# rtc.net
KiCad netlist of a schematic drawn in Altium Designer
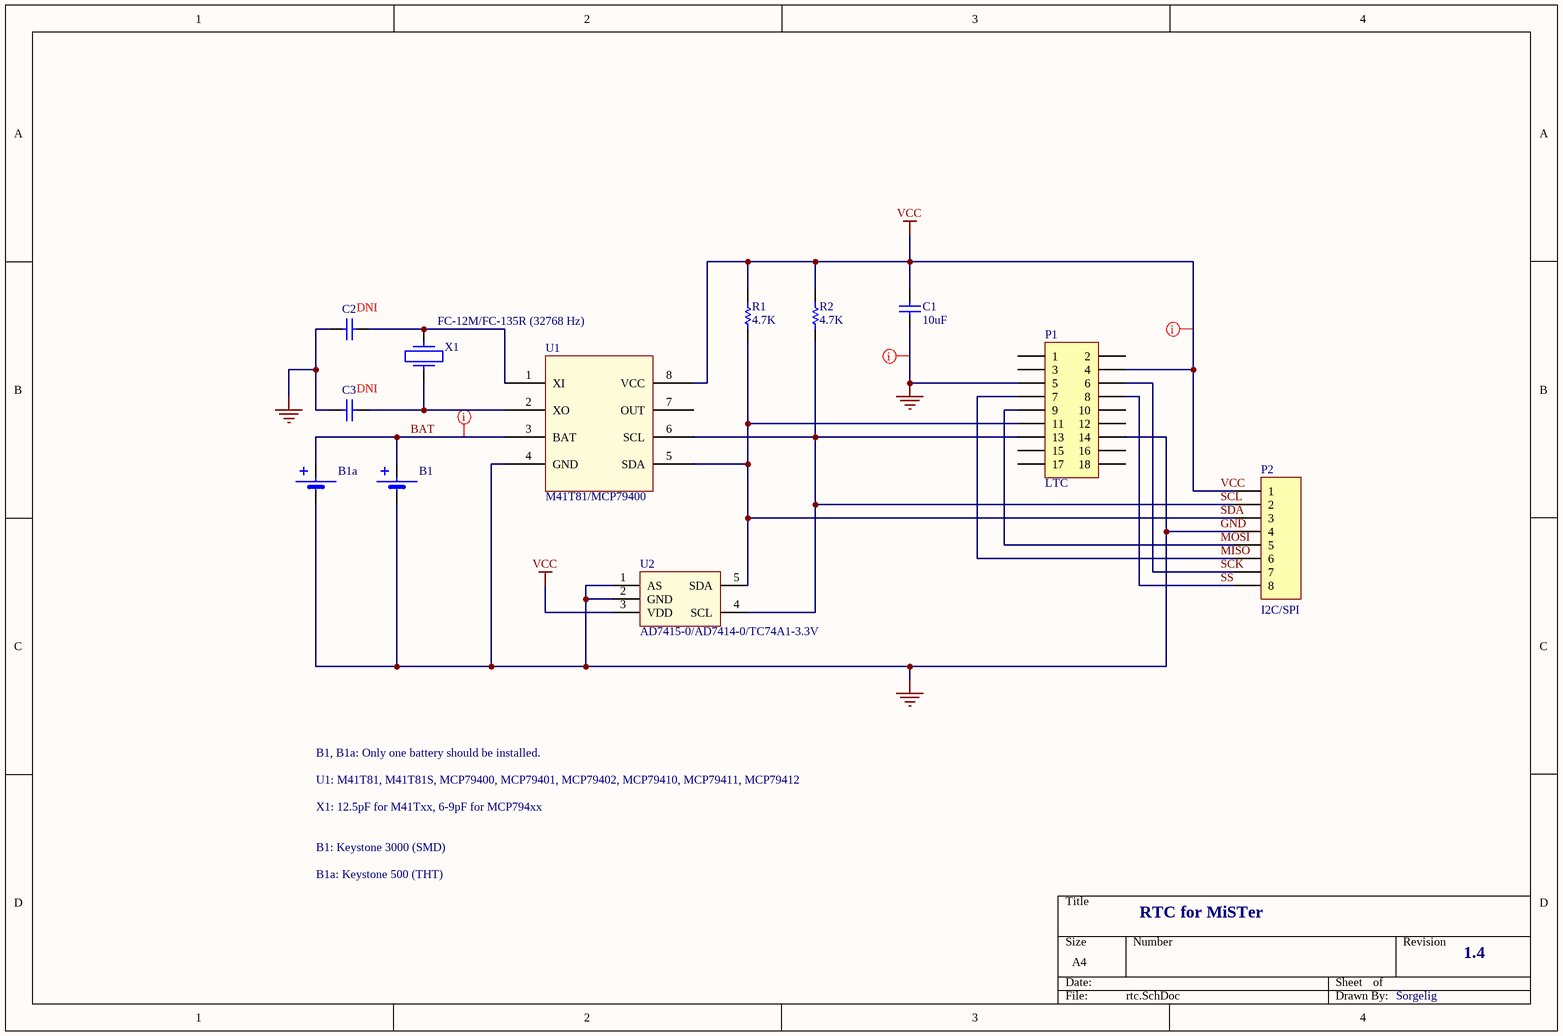
[diagram p0: rtc.SchDoc]

(export (version "E")
  (design (tool "Eeschema 10.0.6"))
  (components
    (comp (ref "B1") (value "*") (footprint "KS3000") (libsource (lib "lib") (part "BAT_KS3000")))
    (comp (ref "B1a") (value "BAT") (footprint "BAT") (libsource (lib "lib") (part "BAT")))
    (comp (ref "C1")
      (value "10uF")
      (footprint "C0805")
      (description "Ceramic Chip Capacitor - Standard")
      (fields (field (name "Comment") "C0805") (field (name "PUBLISHER") "Altium Limited"))
      (libsource (lib "KEMET Chip Capacitor") (part "C0805"))
    )
    (comp (ref "C2")
      (value "C0805")
      (footprint "0805")
      (description "Ceramic Chip Capacitor - Standard")
      (fields (field (name "PUBLISHER") "Altium Limited"))
      (libsource (lib "KEMET Chip Capacitor") (part "C0805"))
    )
    (comp (ref "C3")
      (value "C0805")
      (footprint "0805")
      (description "Ceramic Chip Capacitor - Standard")
      (fields (field (name "PUBLISHER") "Altium Limited"))
      (libsource (lib "KEMET Chip Capacitor") (part "C0805"))
    )
    (comp (ref "P1") (value "LTC") (footprint "hdr9x2") (libsource (lib "lib") (part "HDR9x2")))
    (comp (ref "P2")
      (value "I2C/SPI")
      (footprint "HDR1X8")
      (description "Header, 8-Pin")
      (fields (field (name "PUBLISHER") "Altium Limited"))
      (libsource (lib "Miscellaneous Connectors") (part "Header 8"))
    )
    (comp (ref "R1")
      (value "4.7K")
      (footprint "R0805")
      (fields (field (name "PUBLISHER") "Altium Limited"))
      (libsource (lib "lib") (part "ERJ6RS"))
    )
    (comp (ref "R2")
      (value "4.7K")
      (footprint "R0805")
      (fields (field (name "PUBLISHER") "Altium Limited"))
      (libsource (lib "lib") (part "ERJ6RS"))
    )
    (comp (ref "U1") (value "M41T81/MCP79400") (footprint "SOIC8P") (libsource (lib "lib") (part "M41T")))
    (comp (ref "U2")
      (value "AD7415-0/AD7414-0/TC74A1-3.3V")
      (footprint "SOT23-5")
      (libsource (lib "lib") (part "AD7415"))
    )
    (comp (ref "X1")
      (value "FC-12M/FC-135R (32768 Hz)")
      (footprint "OSC")
      (libsource (lib "lib") (part "OSC"))
    )
  )
  (nets
    (net (code "1") (name "/BAT") (class "Default")
      (node (ref "B1") (pin "2") (pinfunction "2_2") (pintype "passive"))
      (node (ref "B1a") (pin "2") (pinfunction "2_2") (pintype "passive"))
      (node (ref "U1") (pin "3") (pinfunction "BAT_3") (pintype "passive"))
    )
    (net (code "2") (name "/MISO") (class "Default")
      (node (ref "P1") (pin "7") (pinfunction "7_7") (pintype "passive"))
      (node (ref "P2") (pin "6") (pinfunction "6_6") (pintype "passive"))
    )
    (net (code "3") (name "/MOSI") (class "Default")
      (node (ref "P1") (pin "9") (pinfunction "9_9") (pintype "passive"))
      (node (ref "P2") (pin "5") (pinfunction "5_5") (pintype "passive"))
    )
    (net (code "4") (name "/SCK") (class "Default")
      (node (ref "P1") (pin "6") (pinfunction "6_6") (pintype "passive"))
      (node (ref "P2") (pin "7") (pinfunction "7_7") (pintype "passive"))
    )
    (net (code "5") (name "/SCL") (class "Default")
      (node (ref "P1") (pin "13") (pinfunction "13_13") (pintype "passive"))
      (node (ref "P2") (pin "2") (pinfunction "2_2") (pintype "passive"))
      (node (ref "R2") (pin "1") (pinfunction "1_1") (pintype "passive"))
      (node (ref "U1") (pin "6") (pinfunction "SCL_6") (pintype "passive"))
      (node (ref "U2") (pin "4") (pinfunction "SCL_4") (pintype "passive"))
    )
    (net (code "6") (name "/SDA") (class "Default")
      (node (ref "P1") (pin "11") (pinfunction "11_11") (pintype "passive"))
      (node (ref "P2") (pin "3") (pinfunction "3_3") (pintype "passive"))
      (node (ref "R1") (pin "1") (pinfunction "1_1") (pintype "passive"))
      (node (ref "U1") (pin "5") (pinfunction "SDA_5") (pintype "passive"))
      (node (ref "U2") (pin "5") (pinfunction "SDA_5") (pintype "passive"))
    )
    (net (code "7") (name "/SS") (class "Default")
      (node (ref "P1") (pin "8") (pinfunction "8_8") (pintype "passive"))
      (node (ref "P2") (pin "8") (pinfunction "8_8") (pintype "passive"))
    )
    (net (code "8") (name "GND") (class "Default")
      (node (ref "B1") (pin "1") (pinfunction "1_1") (pintype "passive"))
      (node (ref "B1a") (pin "1") (pinfunction "1_1") (pintype "passive"))
      (node (ref "C1") (pin "1") (pinfunction "1_1") (pintype "passive"))
      (node (ref "C2") (pin "1") (pinfunction "1_1") (pintype "passive"))
      (node (ref "C3") (pin "1") (pinfunction "1_1") (pintype "passive"))
      (node (ref "P1") (pin "14") (pinfunction "14_14") (pintype "passive"))
      (node (ref "P1") (pin "5") (pinfunction "5_5") (pintype "passive"))
      (node (ref "P2") (pin "4") (pinfunction "4_4") (pintype "passive"))
      (node (ref "U1") (pin "4") (pinfunction "GND_4") (pintype "passive"))
      (node (ref "U2") (pin "1") (pinfunction "AS_1") (pintype "passive"))
      (node (ref "U2") (pin "2") (pinfunction "GND_2") (pintype "passive"))
    )
    (net (code "9") (name "Net-(U1-XI)") (class "Default")
      (node (ref "C2") (pin "2") (pinfunction "2_2") (pintype "passive"))
      (node (ref "U1") (pin "1") (pinfunction "XI_1") (pintype "passive"))
      (node (ref "X1") (pin "1") (pinfunction "1_1") (pintype "passive"))
    )
    (net (code "10") (name "Net-(U1-XO)") (class "Default")
      (node (ref "C3") (pin "2") (pinfunction "2_2") (pintype "passive"))
      (node (ref "U1") (pin "2") (pinfunction "XO_2") (pintype "passive"))
      (node (ref "X1") (pin "2") (pinfunction "2_2") (pintype "passive"))
    )
    (net (code "11") (name "VCC") (class "Default")
      (node (ref "C1") (pin "2") (pinfunction "2_2") (pintype "passive"))
      (node (ref "P1") (pin "4") (pinfunction "4_4") (pintype "passive"))
      (node (ref "P2") (pin "1") (pinfunction "1_1") (pintype "passive"))
      (node (ref "R1") (pin "2") (pinfunction "2_2") (pintype "passive"))
      (node (ref "R2") (pin "2") (pinfunction "2_2") (pintype "passive"))
      (node (ref "U1") (pin "8") (pinfunction "VCC_8") (pintype "passive"))
      (node (ref "U2") (pin "3") (pinfunction "VDD_3") (pintype "passive"))
    )
    (net (code "12") (name "unconnected-(P1-Pad1)") (class "Default")
      (node (ref "P1") (pin "1") (pinfunction "1_1") (pintype "passive"))
    )
    (net (code "13") (name "unconnected-(P1-Pad2)") (class "Default")
      (node (ref "P1") (pin "2") (pinfunction "2_2") (pintype "passive"))
    )
    (net (code "14") (name "unconnected-(P1-Pad3)") (class "Default")
      (node (ref "P1") (pin "3") (pinfunction "3_3") (pintype "passive"))
    )
    (net (code "15") (name "unconnected-(P1-Pad10)") (class "Default")
      (node (ref "P1") (pin "10") (pinfunction "10_10") (pintype "passive"))
    )
    (net (code "16") (name "unconnected-(P1-Pad12)") (class "Default")
      (node (ref "P1") (pin "12") (pinfunction "12_12") (pintype "passive"))
    )
    (net (code "17") (name "unconnected-(P1-Pad15)") (class "Default")
      (node (ref "P1") (pin "15") (pinfunction "15_15") (pintype "passive"))
    )
    (net (code "18") (name "unconnected-(P1-Pad16)") (class "Default")
      (node (ref "P1") (pin "16") (pinfunction "16_16") (pintype "passive"))
    )
    (net (code "19") (name "unconnected-(P1-Pad17)") (class "Default")
      (node (ref "P1") (pin "17") (pinfunction "17_17") (pintype "passive"))
    )
    (net (code "20") (name "unconnected-(P1-Pad18)") (class "Default")
      (node (ref "P1") (pin "18") (pinfunction "18_18") (pintype "passive"))
    )
    (net (code "21") (name "unconnected-(U1-OUT-Pad7)") (class "Default")
      (node (ref "U1") (pin "7") (pinfunction "OUT_7") (pintype "passive"))
    )
  )
)
